# ugs_preamp.net
KiCad netlist of a schematic drawn in EAGLE
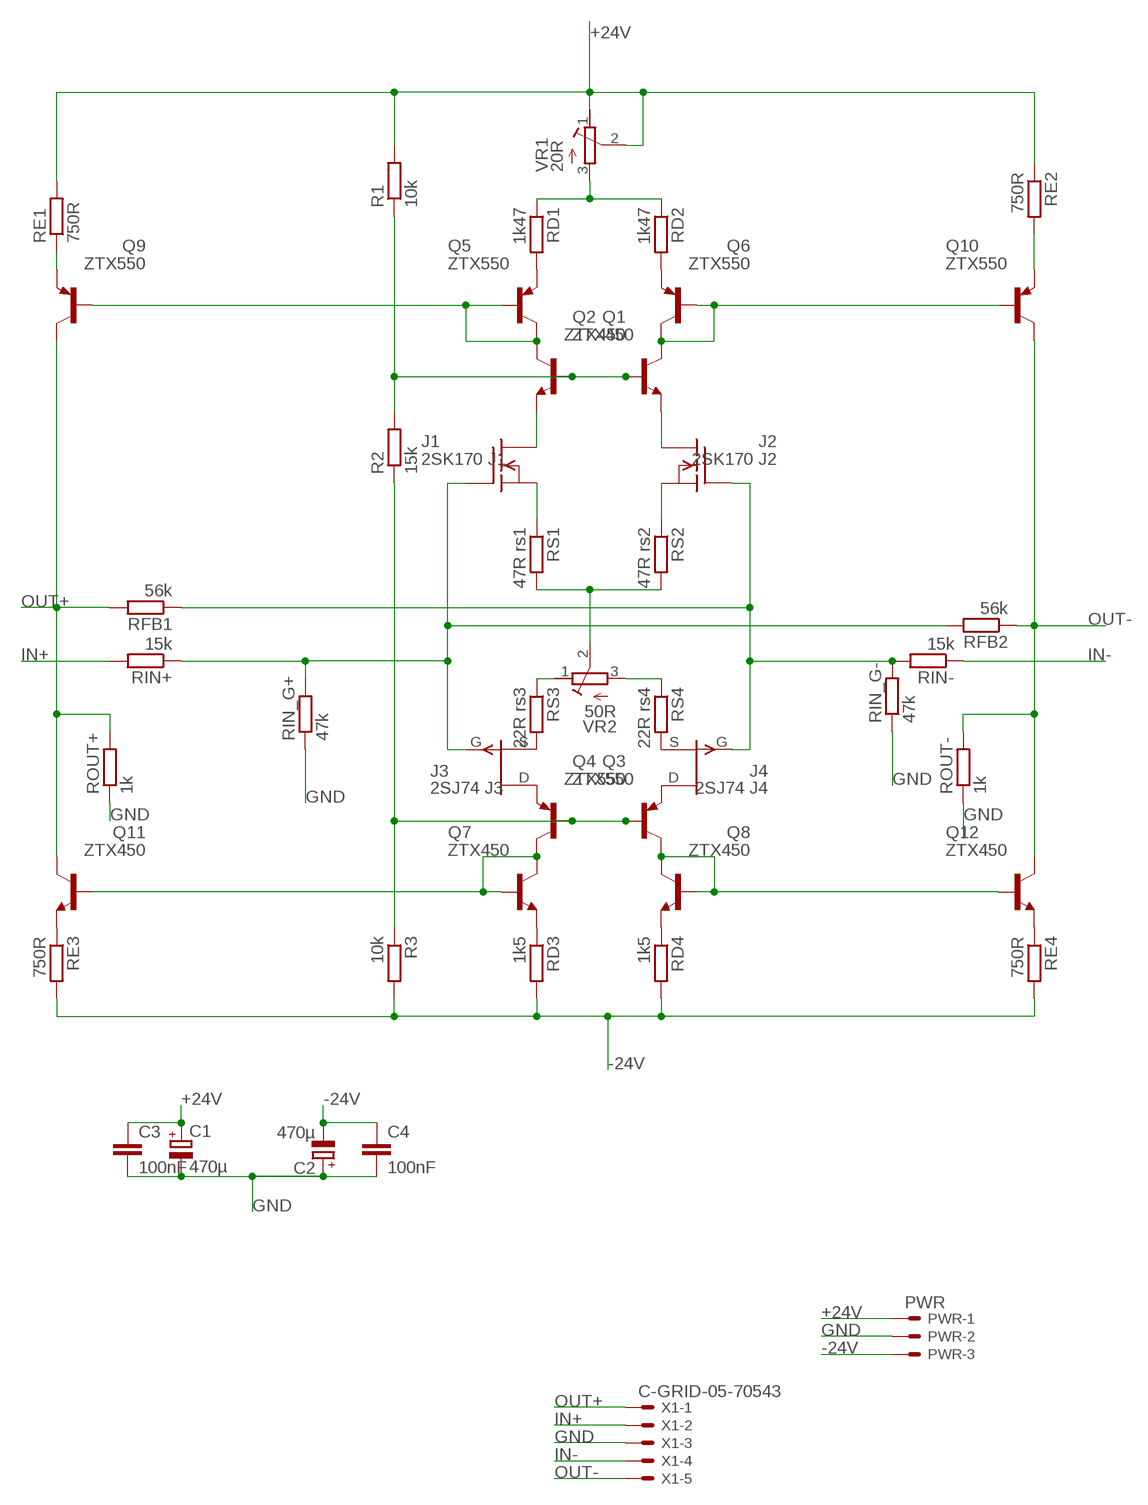
[diagram p0: schematic, sheet 1]

(export (version "E")
  (design (tool "Eeschema 10.0.6"))
  (components
    (comp (ref "C1")
      (value "470µ")
      (footprint "eagle-import:E7,5-16")
      (libsource (lib "eagle-import") (part "CPOL-EUE7.5-16"))
    )
    (comp (ref "C2")
      (value "470µ")
      (footprint "eagle-import:E7,5-16")
      (libsource (lib "eagle-import") (part "CPOL-EUE7.5-16"))
    )
    (comp (ref "C3")
      (value "100nF")
      (footprint "eagle-import:C050-025X075")
      (libsource (lib "eagle-import") (part "C-EU050-025X075"))
    )
    (comp (ref "C4")
      (value "100nF")
      (footprint "eagle-import:C050-025X075")
      (libsource (lib "eagle-import") (part "C-EU050-025X075"))
    )
    (comp (ref "J1")
      (value "2SK170 J1")
      (footprint "eagle-import:TO92")
      (libsource (lib "eagle-import") (part "BSS101"))
    )
    (comp (ref "J2")
      (value "2SK170 J2")
      (footprint "eagle-import:TO92")
      (libsource (lib "eagle-import") (part "BSS101"))
    )
    (comp (ref "J3")
      (value "2SJ74 J3")
      (footprint "eagle-import:TO92")
      (libsource (lib "eagle-import") (part "2N3820"))
    )
    (comp (ref "J4")
      (value "2SJ74 J4")
      (footprint "eagle-import:TO92")
      (libsource (lib "eagle-import") (part "2N3820"))
    )
    (comp (ref "PWR")
      (value "PWR")
      (footprint "eagle-import:70543-03")
      (libsource (lib "eagle-import") (part "C-GRID-03-70543"))
    )
    (comp (ref "Q1")
      (value "ZTX450")
      (footprint "eagle-import:TO92-EBC")
      (libsource (lib "eagle-import") (part "-NPN-TO92-EBC"))
    )
    (comp (ref "Q2")
      (value "ZTX450")
      (footprint "eagle-import:TO92-EBC")
      (libsource (lib "eagle-import") (part "-NPN-TO92-EBC"))
    )
    (comp (ref "Q3")
      (value "ZTX550")
      (footprint "eagle-import:TO92-EBC")
      (libsource (lib "eagle-import") (part "-PNP-TO92-EBCBC328-16"))
    )
    (comp (ref "Q4")
      (value "ZTX550")
      (footprint "eagle-import:TO92-EBC")
      (libsource (lib "eagle-import") (part "-PNP-TO92-EBCBC328-16"))
    )
    (comp (ref "Q5")
      (value "ZTX550")
      (footprint "eagle-import:TO92-EBC")
      (libsource (lib "eagle-import") (part "-PNP-TO92-EBCBC328-16"))
    )
    (comp (ref "Q6")
      (value "ZTX550")
      (footprint "eagle-import:TO92-EBC")
      (libsource (lib "eagle-import") (part "-PNP-TO92-EBCBC328-16"))
    )
    (comp (ref "Q7")
      (value "ZTX450")
      (footprint "eagle-import:TO92-EBC")
      (libsource (lib "eagle-import") (part "-NPN-TO92-EBC"))
    )
    (comp (ref "Q8")
      (value "ZTX450")
      (footprint "eagle-import:TO92-EBC")
      (libsource (lib "eagle-import") (part "-NPN-TO92-EBC"))
    )
    (comp (ref "Q9")
      (value "ZTX550")
      (footprint "eagle-import:TO92-EBC")
      (libsource (lib "eagle-import") (part "-PNP-TO92-EBCBC328-16"))
    )
    (comp (ref "Q10")
      (value "ZTX550")
      (footprint "eagle-import:TO92-EBC")
      (libsource (lib "eagle-import") (part "-PNP-TO92-EBCBC328-16"))
    )
    (comp (ref "Q11")
      (value "ZTX450")
      (footprint "eagle-import:TO92-EBC")
      (libsource (lib "eagle-import") (part "-NPN-TO92-EBC"))
    )
    (comp (ref "Q12")
      (value "ZTX450")
      (footprint "eagle-import:TO92-EBC")
      (libsource (lib "eagle-import") (part "-NPN-TO92-EBC"))
    )
    (comp (ref "R1")
      (value "10k")
      (footprint "eagle-import:0207_10")
      (libsource (lib "eagle-import") (part "R-EU_0207/10"))
    )
    (comp (ref "R2")
      (value "15k")
      (footprint "eagle-import:0207_10")
      (libsource (lib "eagle-import") (part "R-EU_0207/10"))
    )
    (comp (ref "R3")
      (value "10k")
      (footprint "eagle-import:0207_10")
      (libsource (lib "eagle-import") (part "R-EU_0207/10"))
    )
    (comp (ref "RD1")
      (value "1k47")
      (footprint "eagle-import:0207_10")
      (libsource (lib "eagle-import") (part "R-EU_0207/10"))
    )
    (comp (ref "RD2")
      (value "1k47")
      (footprint "eagle-import:0207_10")
      (libsource (lib "eagle-import") (part "R-EU_0207/10"))
    )
    (comp (ref "RD3")
      (value "1k5")
      (footprint "eagle-import:0207_10")
      (libsource (lib "eagle-import") (part "R-EU_0207/10"))
    )
    (comp (ref "RD4")
      (value "1k5")
      (footprint "eagle-import:0207_10")
      (libsource (lib "eagle-import") (part "R-EU_0207/10"))
    )
    (comp (ref "RE1")
      (value "750R")
      (footprint "eagle-import:0207_10")
      (libsource (lib "eagle-import") (part "R-EU_0207/10"))
    )
    (comp (ref "RE2")
      (value "750R")
      (footprint "eagle-import:0207_10")
      (libsource (lib "eagle-import") (part "R-EU_0207/10"))
    )
    (comp (ref "RE3")
      (value "750R")
      (footprint "eagle-import:0207_10")
      (libsource (lib "eagle-import") (part "R-EU_0207/10"))
    )
    (comp (ref "RE4")
      (value "750R")
      (footprint "eagle-import:0207_10")
      (libsource (lib "eagle-import") (part "R-EU_0207/10"))
    )
    (comp (ref "RFB1")
      (value "56k")
      (footprint "eagle-import:0207_10")
      (libsource (lib "eagle-import") (part "R-EU_0207/10"))
    )
    (comp (ref "RFB2")
      (value "56k")
      (footprint "eagle-import:0207_10")
      (libsource (lib "eagle-import") (part "R-EU_0207/10"))
    )
    (comp (ref "RIN+")
      (value "15k")
      (footprint "eagle-import:0207_10")
      (libsource (lib "eagle-import") (part "R-EU_0207/10"))
    )
    (comp (ref "RIN-")
      (value "15k")
      (footprint "eagle-import:0207_10")
      (libsource (lib "eagle-import") (part "R-EU_0207/10"))
    )
    (comp (ref "RIN_G+")
      (value "47k")
      (footprint "eagle-import:0207_10")
      (libsource (lib "eagle-import") (part "R-EU_0207/10"))
    )
    (comp (ref "RIN_G-")
      (value "47k")
      (footprint "eagle-import:0207_10")
      (libsource (lib "eagle-import") (part "R-EU_0207/10"))
    )
    (comp (ref "ROUT+")
      (value "1k")
      (footprint "eagle-import:0207_10")
      (libsource (lib "eagle-import") (part "R-EU_0207/10"))
    )
    (comp (ref "ROUT-")
      (value "1k")
      (footprint "eagle-import:0207_10")
      (libsource (lib "eagle-import") (part "R-EU_0207/10"))
    )
    (comp (ref "RS1")
      (value "47R rs1")
      (footprint "eagle-import:0207_10")
      (libsource (lib "eagle-import") (part "R-EU_0207/10"))
    )
    (comp (ref "RS2")
      (value "47R rs2")
      (footprint "eagle-import:0207_10")
      (libsource (lib "eagle-import") (part "R-EU_0207/10"))
    )
    (comp (ref "RS3")
      (value "22R rs3")
      (footprint "eagle-import:0207_10")
      (libsource (lib "eagle-import") (part "R-EU_0207/10"))
    )
    (comp (ref "RS4")
      (value "22R rs4")
      (footprint "eagle-import:0207_10")
      (libsource (lib "eagle-import") (part "R-EU_0207/10"))
    )
    (comp (ref "VR1")
      (value "20R")
      (footprint "eagle-import:RTRIMT93YA")
      (libsource (lib "eagle-import") (part "R-TRIMMT93YA"))
    )
    (comp (ref "VR2")
      (value "50R")
      (footprint "eagle-import:RTRIMT93YA")
      (libsource (lib "eagle-import") (part "R-TRIMMT93YA"))
    )
    (comp (ref "X1")
      (value "C-GRID-05-70543")
      (footprint "eagle-import:70543-05")
      (libsource (lib "eagle-import") (part "C-GRID-05-70543"))
    )
  )
  (nets
    (net (code "1") (name "/+24V") (class "Default")
      (node (ref "C1") (pin "+") (pinfunction "+_+") (pintype "passive"))
      (node (ref "C3") (pin "1") (pinfunction "1_1") (pintype "passive"))
      (node (ref "PWR") (pin "1") (pinfunction "S_1") (pintype "passive"))
      (node (ref "R1") (pin "2") (pinfunction "2_2") (pintype "passive"))
      (node (ref "RE1") (pin "2") (pinfunction "2_2") (pintype "passive"))
      (node (ref "RE2") (pin "1") (pinfunction "1_1") (pintype "passive"))
      (node (ref "VR1") (pin "1") (pinfunction "E_1") (pintype "passive"))
      (node (ref "VR1") (pin "2") (pinfunction "S_2") (pintype "passive"))
    )
    (net (code "2") (name "/-24V") (class "Default")
      (node (ref "C2") (pin "-") (pinfunction "-_-") (pintype "passive"))
      (node (ref "C4") (pin "1") (pinfunction "1_1") (pintype "passive"))
      (node (ref "PWR") (pin "3") (pinfunction "S_3") (pintype "passive"))
      (node (ref "R3") (pin "2") (pinfunction "2_2") (pintype "passive"))
      (node (ref "RD3") (pin "2") (pinfunction "2_2") (pintype "passive"))
      (node (ref "RD4") (pin "2") (pinfunction "2_2") (pintype "passive"))
      (node (ref "RE3") (pin "2") (pinfunction "2_2") (pintype "passive"))
      (node (ref "RE4") (pin "2") (pinfunction "2_2") (pintype "passive"))
    )
    (net (code "3") (name "/GND") (class "Default")
      (node (ref "C1") (pin "-") (pinfunction "-_-") (pintype "passive"))
      (node (ref "C2") (pin "+") (pinfunction "+_+") (pintype "passive"))
      (node (ref "C3") (pin "2") (pinfunction "2_2") (pintype "passive"))
      (node (ref "C4") (pin "2") (pinfunction "2_2") (pintype "passive"))
      (node (ref "PWR") (pin "2") (pinfunction "S_2") (pintype "passive"))
      (node (ref "RIN_G+") (pin "1") (pinfunction "1_1") (pintype "passive"))
      (node (ref "RIN_G-") (pin "1") (pinfunction "1_1") (pintype "passive"))
      (node (ref "ROUT+") (pin "1") (pinfunction "1_1") (pintype "passive"))
      (node (ref "ROUT-") (pin "1") (pinfunction "1_1") (pintype "passive"))
      (node (ref "X1") (pin "3") (pinfunction "S_3") (pintype "passive"))
    )
    (net (code "4") (name "/IN+") (class "Default")
      (node (ref "RIN+") (pin "2") (pinfunction "2_2") (pintype "passive"))
      (node (ref "X1") (pin "2") (pinfunction "S_2") (pintype "passive"))
    )
    (net (code "5") (name "/IN-") (class "Default")
      (node (ref "RIN-") (pin "1") (pinfunction "1_1") (pintype "passive"))
      (node (ref "X1") (pin "4") (pinfunction "S_4") (pintype "passive"))
    )
    (net (code "6") (name "/OUT+") (class "Default")
      (node (ref "Q11") (pin "C") (pinfunction "C_C") (pintype "passive"))
      (node (ref "Q9") (pin "C") (pinfunction "C_C") (pintype "passive"))
      (node (ref "RFB1") (pin "2") (pinfunction "2_2") (pintype "passive"))
      (node (ref "ROUT+") (pin "2") (pinfunction "2_2") (pintype "passive"))
      (node (ref "X1") (pin "1") (pinfunction "S_1") (pintype "passive"))
    )
    (net (code "7") (name "/OUT-") (class "Default")
      (node (ref "Q10") (pin "C") (pinfunction "C_C") (pintype "passive"))
      (node (ref "Q12") (pin "C") (pinfunction "C_C") (pintype "passive"))
      (node (ref "RFB2") (pin "1") (pinfunction "1_1") (pintype "passive"))
      (node (ref "ROUT-") (pin "2") (pinfunction "2_2") (pintype "passive"))
      (node (ref "X1") (pin "5") (pinfunction "S_5") (pintype "passive"))
    )
    (net (code "8") (name "Net-(J1-D)") (class "Default")
      (node (ref "J1") (pin "3") (pinfunction "D_3") (pintype "passive"))
      (node (ref "Q1") (pin "E") (pinfunction "E_E") (pintype "passive"))
    )
    (net (code "9") (name "Net-(J1-G)") (class "Default")
      (node (ref "J1") (pin "2") (pinfunction "G_2") (pintype "passive"))
      (node (ref "J3") (pin "2") (pinfunction "G_2") (pintype "passive"))
      (node (ref "RFB2") (pin "2") (pinfunction "2_2") (pintype "passive"))
      (node (ref "RIN+") (pin "1") (pinfunction "1_1") (pintype "passive"))
      (node (ref "RIN_G+") (pin "2") (pinfunction "2_2") (pintype "passive"))
    )
    (net (code "10") (name "Net-(J1-S)") (class "Default")
      (node (ref "J1") (pin "1") (pinfunction "S_1") (pintype "passive"))
      (node (ref "RS1") (pin "1") (pinfunction "1_1") (pintype "passive"))
    )
    (net (code "11") (name "Net-(J2-D)") (class "Default")
      (node (ref "J2") (pin "3") (pinfunction "D_3") (pintype "passive"))
      (node (ref "Q2") (pin "E") (pinfunction "E_E") (pintype "passive"))
    )
    (net (code "12") (name "Net-(J2-G)") (class "Default")
      (node (ref "J2") (pin "2") (pinfunction "G_2") (pintype "passive"))
      (node (ref "J4") (pin "2") (pinfunction "G_2") (pintype "passive"))
      (node (ref "RFB1") (pin "1") (pinfunction "1_1") (pintype "passive"))
      (node (ref "RIN-") (pin "2") (pinfunction "2_2") (pintype "passive"))
      (node (ref "RIN_G-") (pin "2") (pinfunction "2_2") (pintype "passive"))
    )
    (net (code "13") (name "Net-(J2-S)") (class "Default")
      (node (ref "J2") (pin "1") (pinfunction "S_1") (pintype "passive"))
      (node (ref "RS2") (pin "1") (pinfunction "1_1") (pintype "passive"))
    )
    (net (code "14") (name "Net-(J3-D)") (class "Default")
      (node (ref "J3") (pin "3") (pinfunction "D_3") (pintype "passive"))
      (node (ref "Q3") (pin "E") (pinfunction "E_E") (pintype "passive"))
    )
    (net (code "15") (name "Net-(J3-S)") (class "Default")
      (node (ref "J3") (pin "1") (pinfunction "S_1") (pintype "passive"))
      (node (ref "RS3") (pin "2") (pinfunction "2_2") (pintype "passive"))
    )
    (net (code "16") (name "Net-(J4-D)") (class "Default")
      (node (ref "J4") (pin "3") (pinfunction "D_3") (pintype "passive"))
      (node (ref "Q4") (pin "E") (pinfunction "E_E") (pintype "passive"))
    )
    (net (code "17") (name "Net-(J4-S)") (class "Default")
      (node (ref "J4") (pin "1") (pinfunction "S_1") (pintype "passive"))
      (node (ref "RS4") (pin "2") (pinfunction "2_2") (pintype "passive"))
    )
    (net (code "18") (name "Net-(Q1-PadB)") (class "Default")
      (node (ref "Q1") (pin "B") (pinfunction "B_B") (pintype "passive"))
      (node (ref "Q2") (pin "B") (pinfunction "B_B") (pintype "passive"))
      (node (ref "R1") (pin "1") (pinfunction "1_1") (pintype "passive"))
      (node (ref "R2") (pin "2") (pinfunction "2_2") (pintype "passive"))
    )
    (net (code "19") (name "Net-(Q1-PadC)") (class "Default")
      (node (ref "Q1") (pin "C") (pinfunction "C_C") (pintype "passive"))
      (node (ref "Q5") (pin "B") (pinfunction "B_B") (pintype "passive"))
      (node (ref "Q5") (pin "C") (pinfunction "C_C") (pintype "passive"))
      (node (ref "Q9") (pin "B") (pinfunction "B_B") (pintype "passive"))
    )
    (net (code "20") (name "Net-(Q3-PadB)") (class "Default")
      (node (ref "Q3") (pin "B") (pinfunction "B_B") (pintype "passive"))
      (node (ref "Q4") (pin "B") (pinfunction "B_B") (pintype "passive"))
      (node (ref "R2") (pin "1") (pinfunction "1_1") (pintype "passive"))
      (node (ref "R3") (pin "1") (pinfunction "1_1") (pintype "passive"))
    )
    (net (code "21") (name "Net-(Q5-PadE)") (class "Default")
      (node (ref "Q5") (pin "E") (pinfunction "E_E") (pintype "passive"))
      (node (ref "RD1") (pin "2") (pinfunction "2_2") (pintype "passive"))
    )
    (net (code "22") (name "Net-(Q6-PadE)") (class "Default")
      (node (ref "Q6") (pin "E") (pinfunction "E_E") (pintype "passive"))
      (node (ref "RD2") (pin "2") (pinfunction "2_2") (pintype "passive"))
    )
    (net (code "23") (name "Net-(Q7-PadE)") (class "Default")
      (node (ref "Q7") (pin "E") (pinfunction "E_E") (pintype "passive"))
      (node (ref "RD3") (pin "1") (pinfunction "1_1") (pintype "passive"))
    )
    (net (code "24") (name "Net-(Q8-PadE)") (class "Default")
      (node (ref "Q8") (pin "E") (pinfunction "E_E") (pintype "passive"))
      (node (ref "RD4") (pin "1") (pinfunction "1_1") (pintype "passive"))
    )
    (net (code "25") (name "Net-(Q9-PadE)") (class "Default")
      (node (ref "Q9") (pin "E") (pinfunction "E_E") (pintype "passive"))
      (node (ref "RE1") (pin "1") (pinfunction "1_1") (pintype "passive"))
    )
    (net (code "26") (name "Net-(Q10-PadB)") (class "Default")
      (node (ref "Q10") (pin "B") (pinfunction "B_B") (pintype "passive"))
      (node (ref "Q2") (pin "C") (pinfunction "C_C") (pintype "passive"))
      (node (ref "Q6") (pin "B") (pinfunction "B_B") (pintype "passive"))
      (node (ref "Q6") (pin "C") (pinfunction "C_C") (pintype "passive"))
    )
    (net (code "27") (name "Net-(Q10-PadE)") (class "Default")
      (node (ref "Q10") (pin "E") (pinfunction "E_E") (pintype "passive"))
      (node (ref "RE2") (pin "2") (pinfunction "2_2") (pintype "passive"))
    )
    (net (code "28") (name "Net-(Q11-PadB)") (class "Default")
      (node (ref "Q11") (pin "B") (pinfunction "B_B") (pintype "passive"))
      (node (ref "Q3") (pin "C") (pinfunction "C_C") (pintype "passive"))
      (node (ref "Q7") (pin "B") (pinfunction "B_B") (pintype "passive"))
      (node (ref "Q7") (pin "C") (pinfunction "C_C") (pintype "passive"))
    )
    (net (code "29") (name "Net-(Q11-PadE)") (class "Default")
      (node (ref "Q11") (pin "E") (pinfunction "E_E") (pintype "passive"))
      (node (ref "RE3") (pin "1") (pinfunction "1_1") (pintype "passive"))
    )
    (net (code "30") (name "Net-(Q12-PadB)") (class "Default")
      (node (ref "Q12") (pin "B") (pinfunction "B_B") (pintype "passive"))
      (node (ref "Q4") (pin "C") (pinfunction "C_C") (pintype "passive"))
      (node (ref "Q8") (pin "B") (pinfunction "B_B") (pintype "passive"))
      (node (ref "Q8") (pin "C") (pinfunction "C_C") (pintype "passive"))
    )
    (net (code "31") (name "Net-(Q12-PadE)") (class "Default")
      (node (ref "Q12") (pin "E") (pinfunction "E_E") (pintype "passive"))
      (node (ref "RE4") (pin "1") (pinfunction "1_1") (pintype "passive"))
    )
    (net (code "32") (name "Net-(VR1-A)") (class "Default")
      (node (ref "RD1") (pin "1") (pinfunction "1_1") (pintype "passive"))
      (node (ref "RD2") (pin "1") (pinfunction "1_1") (pintype "passive"))
      (node (ref "VR1") (pin "3") (pinfunction "A_3") (pintype "passive"))
    )
    (net (code "33") (name "Net-(VR2-A)") (class "Default")
      (node (ref "RS4") (pin "1") (pinfunction "1_1") (pintype "passive"))
      (node (ref "VR2") (pin "3") (pinfunction "A_3") (pintype "passive"))
    )
    (net (code "34") (name "Net-(VR2-E)") (class "Default")
      (node (ref "RS3") (pin "1") (pinfunction "1_1") (pintype "passive"))
      (node (ref "VR2") (pin "1") (pinfunction "E_1") (pintype "passive"))
    )
    (net (code "35") (name "Net-(VR2-S)") (class "Default")
      (node (ref "RS1") (pin "2") (pinfunction "2_2") (pintype "passive"))
      (node (ref "RS2") (pin "2") (pinfunction "2_2") (pintype "passive"))
      (node (ref "VR2") (pin "2") (pinfunction "S_2") (pintype "passive"))
    )
  )
)
